# waterius-homemade.net
KiCad netlist of a schematic drawn in EAGLE
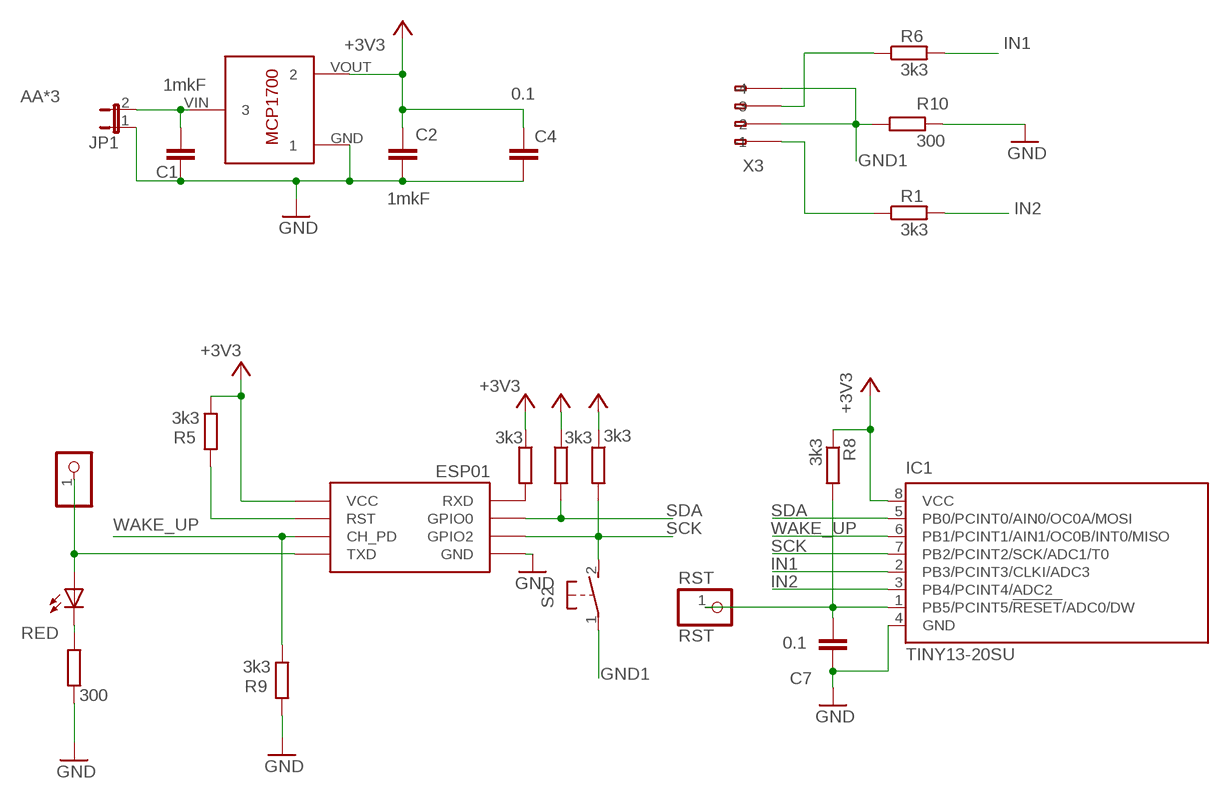
[diagram p0: schematic, sheet 1]

(export (version "E")
  (design (tool "Eeschema 10.0.6"))
  (components
    (comp (ref "C1")
      (value "1mkF")
      (footprint "eagle-import:C0805")
      (libsource (lib "eagle-import") (part "resistor_348_C-EUC0805"))
    )
    (comp (ref "C2")
      (value "1mkF")
      (footprint "eagle-import:C0805")
      (libsource (lib "eagle-import") (part "resistor_348_C-EUC0805"))
    )
    (comp (ref "C4")
      (value "0.1")
      (footprint "eagle-import:C0805")
      (libsource (lib "eagle-import") (part "C-EUC0805"))
    )
    (comp (ref "C7")
      (value "0.1")
      (footprint "eagle-import:C0805")
      (libsource (lib "eagle-import") (part "resistor_348_C-EUC0805"))
    )
    (comp (ref "IC1")
      (value "TINY13-20SU")
      (footprint "eagle-import:8S2")
      (fields (field (name "MPN") "ATTINY13-20SU"))
      (libsource (lib "eagle-import") (part "TINY13SU-20"))
    )
    (comp (ref "JP1")
      (value "JP1E")
      (footprint "eagle-import:JP1")
      (libsource (lib "eagle-import") (part "JP1E"))
    )
    (comp (ref "LED1")
      (value "RED")
      (footprint "eagle-import:LED3MM")
      (libsource (lib "eagle-import") (part "LED3MM"))
    )
    (comp (ref "LOG")
      (value "LOG")
      (footprint "eagle-import:1X01")
      (libsource (lib "eagle-import") (part "PINHD-1X1"))
    )
    (comp (ref "R1")
      (value "3k3")
      (footprint "eagle-import:M0805")
      (fields (field (name "SPICEPREFIX") "R"))
      (libsource (lib "eagle-import") (part "resistor_348_R-EU_M0805"))
    )
    (comp (ref "R2")
      (value "3k3")
      (footprint "eagle-import:R0805")
      (fields (field (name "OM") "3k6"))
      (libsource (lib "eagle-import") (part "R-EU_R0805"))
    )
    (comp (ref "R3")
      (value "3k3")
      (footprint "eagle-import:R0805")
      (fields (field (name "OM") "3k6"))
      (libsource (lib "eagle-import") (part "rcl_334_R-EU_R0805"))
    )
    (comp (ref "R4")
      (value "300")
      (footprint "eagle-import:R0805")
      (fields (field (name "OM") "200"))
      (libsource (lib "eagle-import") (part "rcl_334_R-EU_R0805"))
    )
    (comp (ref "R5")
      (value "3k3")
      (footprint "eagle-import:R0805")
      (fields (field (name "OM") "3k6"))
      (libsource (lib "eagle-import") (part "R-EU_R0805"))
    )
    (comp (ref "R6")
      (value "3k3")
      (footprint "eagle-import:M0805")
      (libsource (lib "eagle-import") (part "resistor_348_R-EU_M0805"))
    )
    (comp (ref "R7")
      (value "3k3")
      (footprint "eagle-import:R0805")
      (fields (field (name "OM") "3k6"))
      (libsource (lib "eagle-import") (part "R-EU_R0805"))
    )
    (comp (ref "R8")
      (value "3k3")
      (footprint "eagle-import:R0805")
      (fields (field (name "OM") "3k6"))
      (libsource (lib "eagle-import") (part "rcl_334_R-EU_R0805"))
    )
    (comp (ref "R9")
      (value "3k3")
      (footprint "eagle-import:R0805")
      (fields (field (name "OM") "3k6"))
      (libsource (lib "eagle-import") (part "R-EU_R0805"))
    )
    (comp (ref "R10")
      (value "300")
      (footprint "eagle-import:M0805")
      (libsource (lib "eagle-import") (part "resistor_348_R-EU_M0805"))
    )
    (comp (ref "RST")
      (value "RST")
      (footprint "eagle-import:1X01")
      (libsource (lib "eagle-import") (part "PINHD-1X1"))
    )
    (comp (ref "S2")
      (value "31-XX")
      (footprint "eagle-import:B3F-31XX")
      (fields (field (name "MPN") "B3F-3100"))
      (libsource (lib "eagle-import") (part "31-XX"))
    )
    (comp (ref "U$1")
      (value "ESP01")
      (footprint "eagle-import:ESP01")
      (libsource (lib "eagle-import") (part "ESP01"))
    )
    (comp (ref "U$2")
      (value "MCP1700T-3302E/TT")
      (footprint "eagle-import:MCP1700T-3302E_TT")
      (libsource (lib "eagle-import") (part "MCP1700T-3302E/TT"))
    )
    (comp (ref "X3")
      (value "233-104")
      (footprint "eagle-import:233-104")
      (libsource (lib "eagle-import") (part "233-104"))
    )
  )
  (nets
    (net (code "1") (name "+3V3") (class "Default")
      (node (ref "C2") (pin "1") (pinfunction "1_1") (pintype "passive"))
      (node (ref "C4") (pin "1") (pinfunction "1_1") (pintype "passive"))
      (node (ref "IC1") (pin "8") (pinfunction "VCC_8") (pintype "power_in"))
      (node (ref "R2") (pin "1") (pinfunction "1_1") (pintype "passive"))
      (node (ref "R3") (pin "1") (pinfunction "1_1") (pintype "passive"))
      (node (ref "R5") (pin "1") (pinfunction "1_1") (pintype "passive"))
      (node (ref "R7") (pin "1") (pinfunction "1_1") (pintype "passive"))
      (node (ref "R8") (pin "1") (pinfunction "1_1") (pintype "passive"))
      (node (ref "U$1") (pin "VCC") (pinfunction "VCC_VCC") (pintype "bidirectional"))
      (node (ref "U$2") (pin "VOUT") (pinfunction "2_VOUT") (pintype "bidirectional"))
    )
    (net (code "2") (name "/AA*3") (class "Default")
      (node (ref "C1") (pin "1") (pinfunction "1_1") (pintype "passive"))
      (node (ref "JP1") (pin "2") (pinfunction "2_2") (pintype "passive"))
      (node (ref "U$2") (pin "VIN") (pinfunction "3_VIN") (pintype "bidirectional"))
    )
    (net (code "3") (name "/GND1") (class "Default")
      (node (ref "R10") (pin "1") (pinfunction "1_1") (pintype "passive"))
      (node (ref "S2") (pin "1") (pinfunction "P_1") (pintype "passive"))
      (node (ref "X3") (pin "A2") (pinfunction "-2_A2") (pintype "passive"))
      (node (ref "X3") (pin "A4") (pinfunction "-4_A4") (pintype "passive"))
    )
    (net (code "4") (name "/IN1") (class "Default")
      (node (ref "IC1") (pin "2") (pinfunction "PB3/PCINT3/CLKI/ADC3_2") (pintype "bidirectional"))
      (node (ref "R6") (pin "2") (pinfunction "2_2") (pintype "passive"))
    )
    (net (code "5") (name "/IN2") (class "Default")
      (node (ref "IC1") (pin "3") (pinfunction "PB4/PCINT4/ADC2_3") (pintype "bidirectional"))
      (node (ref "R1") (pin "2") (pinfunction "2_2") (pintype "passive"))
    )
    (net (code "6") (name "/SCK") (class "Default")
      (node (ref "IC1") (pin "7") (pinfunction "PB2/PCINT2/SCK/ADC1/T0_7") (pintype "bidirectional"))
      (node (ref "R2") (pin "2") (pinfunction "2_2") (pintype "passive"))
      (node (ref "S2") (pin "2") (pinfunction "S_2") (pintype "passive"))
      (node (ref "U$1") (pin "GPIO2") (pinfunction "GPIO2_GPIO2") (pintype "bidirectional"))
    )
    (net (code "7") (name "/SDA") (class "Default")
      (node (ref "IC1") (pin "5") (pinfunction "PB0/PCINT0/AIN0/OC0A/MOSI_5") (pintype "bidirectional"))
      (node (ref "R3") (pin "2") (pinfunction "2_2") (pintype "passive"))
      (node (ref "U$1") (pin "GPIO0") (pinfunction "GPIO0_GPIO0") (pintype "bidirectional"))
    )
    (net (code "8") (name "/WAKE_UP") (class "Default")
      (node (ref "IC1") (pin "6") (pinfunction "PB1/PCINT1/AIN1/OC0B/INT0/MISO_6") (pintype "bidirectional"))
      (node (ref "R9") (pin "1") (pinfunction "1_1") (pintype "passive"))
      (node (ref "U$1") (pin "CH_PD") (pinfunction "CH_PD_CH_PD") (pintype "bidirectional"))
    )
    (net (code "9") (name "GND") (class "Default")
      (node (ref "C1") (pin "2") (pinfunction "2_2") (pintype "passive"))
      (node (ref "C2") (pin "2") (pinfunction "2_2") (pintype "passive"))
      (node (ref "C4") (pin "2") (pinfunction "2_2") (pintype "passive"))
      (node (ref "C7") (pin "1") (pinfunction "1_1") (pintype "passive"))
      (node (ref "IC1") (pin "4") (pinfunction "GND_4") (pintype "power_in"))
      (node (ref "JP1") (pin "1") (pinfunction "1_1") (pintype "passive"))
      (node (ref "R10") (pin "2") (pinfunction "2_2") (pintype "passive"))
      (node (ref "R4") (pin "2") (pinfunction "2_2") (pintype "passive"))
      (node (ref "R9") (pin "2") (pinfunction "2_2") (pintype "passive"))
      (node (ref "U$1") (pin "GND") (pinfunction "GND_GND") (pintype "bidirectional"))
      (node (ref "U$2") (pin "GND") (pinfunction "1_GND") (pintype "bidirectional"))
    )
    (net (code "10") (name "Net-(IC1-PB5{slash}PCINT5{slash}~{RESET}{slash}ADC0{slash}DW)") (class "Default")
      (node (ref "C7") (pin "2") (pinfunction "2_2") (pintype "passive"))
      (node (ref "IC1") (pin "1") (pinfunction "PB5/PCINT5/~{RESET}/ADC0/DW_1") (pintype "bidirectional"))
      (node (ref "R8") (pin "2") (pinfunction "2_2") (pintype "passive"))
      (node (ref "RST") (pin "1") (pinfunction "1_1") (pintype "passive"))
    )
    (net (code "11") (name "Net-(LED1-C)") (class "Default")
      (node (ref "LED1") (pin "K") (pinfunction "C_K") (pintype "passive"))
      (node (ref "R4") (pin "1") (pinfunction "1_1") (pintype "passive"))
    )
    (net (code "12") (name "Net-(R5-Pad2)") (class "Default")
      (node (ref "R5") (pin "2") (pinfunction "2_2") (pintype "passive"))
      (node (ref "U$1") (pin "RST") (pinfunction "RST_RST") (pintype "bidirectional"))
    )
    (net (code "13") (name "Net-(U$1-RXD)") (class "Default")
      (node (ref "R7") (pin "2") (pinfunction "2_2") (pintype "passive"))
      (node (ref "U$1") (pin "RX") (pinfunction "RXD_RX") (pintype "bidirectional"))
    )
    (net (code "14") (name "Net-(U$1-TXD)") (class "Default")
      (node (ref "LED1") (pin "A") (pinfunction "A_A") (pintype "passive"))
      (node (ref "LOG") (pin "1") (pinfunction "1_1") (pintype "passive"))
      (node (ref "U$1") (pin "TX") (pinfunction "TXD_TX") (pintype "bidirectional"))
    )
    (net (code "15") (name "Net-(X3--1)") (class "Default")
      (node (ref "R1") (pin "1") (pinfunction "1_1") (pintype "passive"))
      (node (ref "X3") (pin "A1") (pinfunction "-1_A1") (pintype "passive"))
    )
    (net (code "16") (name "Net-(X3--3)") (class "Default")
      (node (ref "R6") (pin "1") (pinfunction "1_1") (pintype "passive"))
      (node (ref "X3") (pin "A3") (pinfunction "-3_A3") (pintype "passive"))
    )
    (net (code "17") (name "unconnected-(X3-B-1-PadB1)") (class "Default")
      (node (ref "X3") (pin "B1") (pinfunction "B-1_B1") (pintype "passive"))
    )
    (net (code "18") (name "unconnected-(X3-B-2-PadB2)") (class "Default")
      (node (ref "X3") (pin "B2") (pinfunction "B-2_B2") (pintype "passive"))
    )
    (net (code "19") (name "unconnected-(X3-B-3-PadB3)") (class "Default")
      (node (ref "X3") (pin "B3") (pinfunction "B-3_B3") (pintype "passive"))
    )
    (net (code "20") (name "unconnected-(X3-B-4-PadB4)") (class "Default")
      (node (ref "X3") (pin "B4") (pinfunction "B-4_B4") (pintype "passive"))
    )
  )
)
